# 8_DAC_and_MIC.net
KiCad netlist of a schematic drawn in Altium Designer
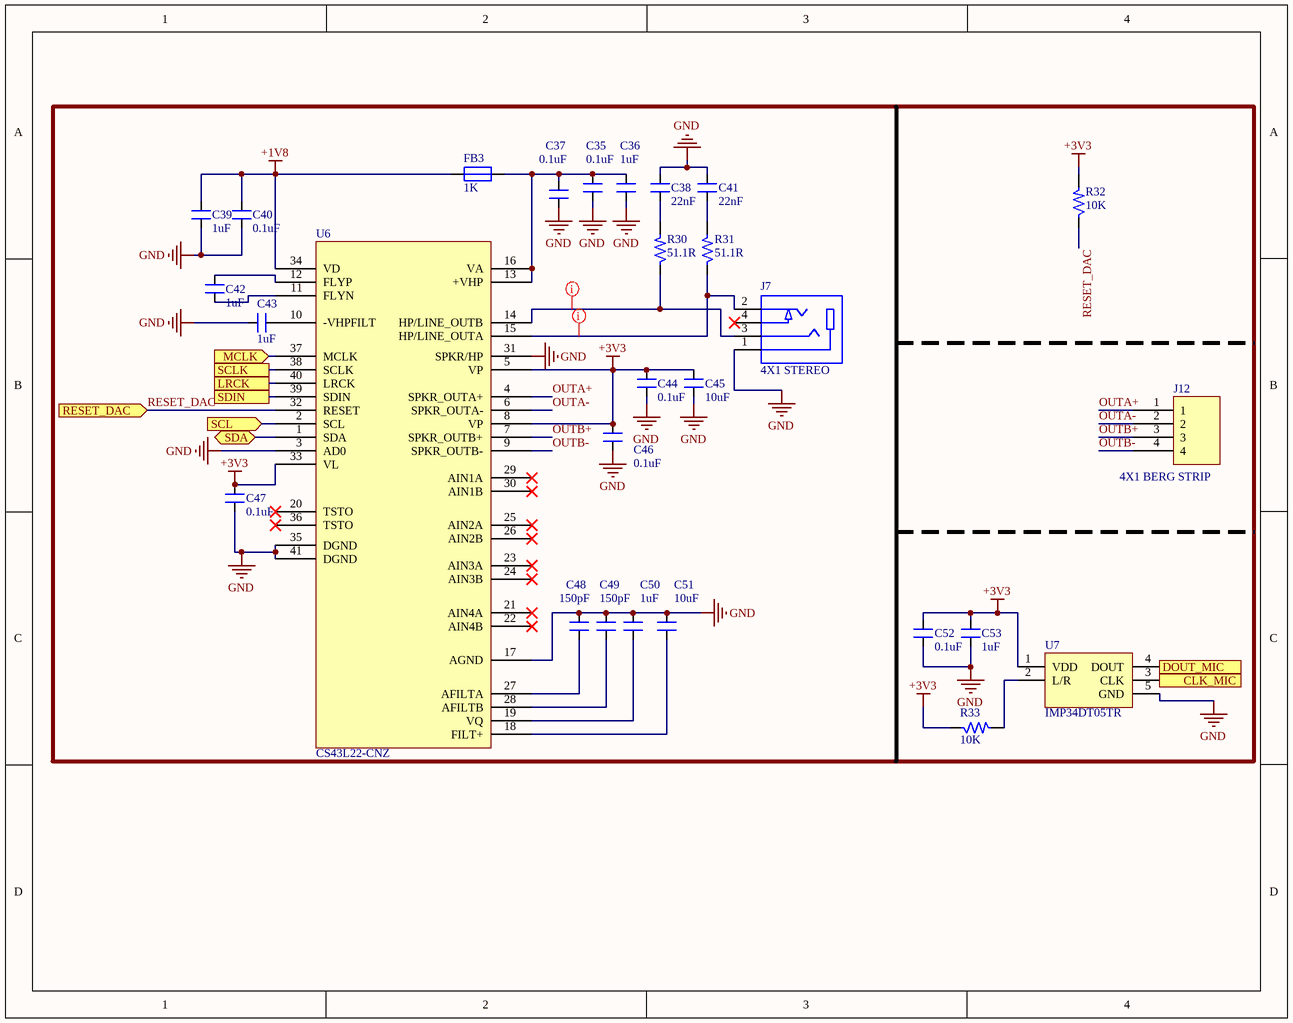
[diagram p0: [8] DAC and MIC.SchDoc]

(export (version "E")
  (design (tool "Eeschema 10.0.6"))
  (components
    (comp (ref "C35")
      (value "0.1uF")
      (footprint "CAP_0805")
      (description "0.1µF ±10% 50V Ceramic Capacitor X7R 0805 (2012 Metric)")
      (fields
        (field (name "MANUFACTURER") "Samsung")
        (field (name "MANUFACTURER PART NUMBER") "CL21B104KBCNNNC")
      )
      (libsource (lib "ESTEEMPCBLIB") (part "CAP_0.1uF-50V-10%-0805"))
    )
    (comp (ref "C36")
      (value "1uF")
      (footprint "CAP_0805")
      (description "1µF ±5% 50V Ceramic Capacitor X7R 0805 (2012 Metric)")
      (fields
        (field (name "MANUFACTURER") "Samsung")
        (field (name "MANUFACTURER PART NUMBER") "CC0805JKX7R9BB105")
      )
      (libsource (lib "ESTEEMPCBLIB") (part "CAP_1uF-50V-5%-0805"))
    )
    (comp (ref "C37")
      (value "0.1uF")
      (footprint "CAP_0805")
      (description "0.1µF ±10% 50V Ceramic Capacitor X7R 0805 (2012 Metric)")
      (fields
        (field (name "MANUFACTURER") "Samsung")
        (field (name "MANUFACTURER PART NUMBER") "CL21B104KBCNNNC")
      )
      (libsource (lib "ESTEEMPCBLIB") (part "CAP_0.1uF-50V-10%-0805"))
    )
    (comp (ref "C38")
      (value "22nF")
      (footprint "CAP_0805")
      (description "0.022µF ±10% 50V Ceramic Capacitor X7R 0805 (2012 Metric)")
      (fields
        (field (name "MANUFACTURER") "Samsung Electro-Mechanics")
        (field (name "MANUFACTURER PART NUMBER") "CL21B223KBANNNC")
      )
      (libsource (lib "ESTEEMPCBLIB") (part "CAP_22nF-50V-10%-0805"))
    )
    (comp (ref "C39")
      (value "1uF")
      (footprint "CAP_0805")
      (description "1µF ±5% 50V Ceramic Capacitor X7R 0805 (2012 Metric)")
      (fields
        (field (name "MANUFACTURER") "Samsung")
        (field (name "MANUFACTURER PART NUMBER") "CC0805JKX7R9BB105")
      )
      (libsource (lib "ESTEEMPCBLIB") (part "CAP_1uF-50V-5%-0805"))
    )
    (comp (ref "C40")
      (value "0.1uF")
      (footprint "CAP_0805")
      (description "0.1µF ±10% 50V Ceramic Capacitor X7R 0805 (2012 Metric)")
      (fields
        (field (name "MANUFACTURER") "Samsung")
        (field (name "MANUFACTURER PART NUMBER") "CL21B104KBCNNNC")
      )
      (libsource (lib "ESTEEMPCBLIB") (part "CAP_0.1uF-50V-10%-0805"))
    )
    (comp (ref "C41")
      (value "22nF")
      (footprint "CAP_0805")
      (description "0.022µF ±10% 50V Ceramic Capacitor X7R 0805 (2012 Metric)")
      (fields
        (field (name "MANUFACTURER") "Samsung Electro-Mechanics")
        (field (name "MANUFACTURER PART NUMBER") "CL21B223KBANNNC")
      )
      (libsource (lib "ESTEEMPCBLIB") (part "CAP_22nF-50V-10%-0805"))
    )
    (comp (ref "C42")
      (value "1uF")
      (footprint "CAP_0805")
      (description "1µF ±5% 50V Ceramic Capacitor X7R 0805 (2012 Metric)")
      (fields
        (field (name "MANUFACTURER") "Samsung")
        (field (name "MANUFACTURER PART NUMBER") "CC0805JKX7R9BB105")
      )
      (libsource (lib "ESTEEMPCBLIB") (part "CAP_1uF-50V-5%-0805"))
    )
    (comp (ref "C43")
      (value "1uF")
      (footprint "CAP_0805")
      (description "1µF ±5% 50V Ceramic Capacitor X7R 0805 (2012 Metric)")
      (fields
        (field (name "MANUFACTURER") "Samsung")
        (field (name "MANUFACTURER PART NUMBER") "CC0805JKX7R9BB105")
      )
      (libsource (lib "ESTEEMPCBLIB") (part "CAP_1uF-50V-5%-0805"))
    )
    (comp (ref "C44")
      (value "0.1uF")
      (footprint "CAP_0805")
      (description "0.1µF ±10% 50V Ceramic Capacitor X7R 0805 (2012 Metric)")
      (fields
        (field (name "MANUFACTURER") "Samsung")
        (field (name "MANUFACTURER PART NUMBER") "CL21B104KBCNNNC")
      )
      (libsource (lib "ESTEEMPCBLIB") (part "CAP_0.1uF-50V-10%-0805"))
    )
    (comp (ref "C45")
      (value "10uF")
      (footprint "CAP_1206")
      (description "10µF ±10% 50V Ceramic Capacitor X7R 1206 (3216 Metric)")
      (fields
        (field (name "MANUFACTURER") "KEMET")
        (field (name "MANUFACTURER PART NUMBER") "CL31B106KBHNNNE")
      )
      (libsource (lib "ESTEEMPCBLIB") (part "CAP_10uF-50V-10%-1206"))
    )
    (comp (ref "C46")
      (value "0.1uF")
      (footprint "CAP_0805")
      (description "0.1µF ±10% 50V Ceramic Capacitor X7R 0805 (2012 Metric)")
      (fields
        (field (name "MANUFACTURER") "Samsung")
        (field (name "MANUFACTURER PART NUMBER") "CL21B104KBCNNNC")
      )
      (libsource (lib "ESTEEMPCBLIB") (part "CAP_0.1uF-50V-10%-0805"))
    )
    (comp (ref "C47")
      (value "0.1uF")
      (footprint "CAP_0805")
      (description "0.1µF ±10% 50V Ceramic Capacitor X7R 0805 (2012 Metric)")
      (fields
        (field (name "MANUFACTURER") "Samsung")
        (field (name "MANUFACTURER PART NUMBER") "CL21B104KBCNNNC")
      )
      (libsource (lib "ESTEEMPCBLIB") (part "CAP_0.1uF-50V-10%-0805"))
    )
    (comp (ref "C48")
      (value "150pF")
      (footprint "CAP_0805")
      (description "150pF ±10% 50V Ceramic Capacitor C0G, NP0 0805 (2012 Metric)")
      (fields
        (field (name "MANUFACTURER") "AVX Corporation")
        (field (name "MANUFACTURER PART NUMBER") "08055A151KAT2A")
      )
      (libsource (lib "ESTEEMPCBLIB") (part "CAP_150pF-50V-10%-0805"))
    )
    (comp (ref "C49")
      (value "150pF")
      (footprint "CAP_0805")
      (description "150pF ±10% 50V Ceramic Capacitor C0G, NP0 0805 (2012 Metric)")
      (fields
        (field (name "MANUFACTURER") "AVX Corporation")
        (field (name "MANUFACTURER PART NUMBER") "08055A151KAT2A")
      )
      (libsource (lib "ESTEEMPCBLIB") (part "CAP_150pF-50V-10%-0805"))
    )
    (comp (ref "C50")
      (value "1uF")
      (footprint "CAP_0805")
      (description "1µF ±5% 50V Ceramic Capacitor X7R 0805 (2012 Metric)")
      (fields
        (field (name "MANUFACTURER") "Samsung")
        (field (name "MANUFACTURER PART NUMBER") "CC0805JKX7R9BB105")
      )
      (libsource (lib "ESTEEMPCBLIB") (part "CAP_1uF-50V-5%-0805"))
    )
    (comp (ref "C51")
      (value "10uF")
      (footprint "CAP_1206")
      (description "10µF ±10% 50V Ceramic Capacitor X7R 1206 (3216 Metric)")
      (fields
        (field (name "MANUFACTURER") "KEMET")
        (field (name "MANUFACTURER PART NUMBER") "CL31B106KBHNNNE")
      )
      (libsource (lib "ESTEEMPCBLIB") (part "CAP_10uF-50V-10%-1206"))
    )
    (comp (ref "C52")
      (value "0.1uF")
      (footprint "CAP_0805")
      (description "0.1µF ±10% 50V Ceramic Capacitor X7R 0805 (2012 Metric)")
      (fields
        (field (name "MANUFACTURER") "Samsung")
        (field (name "MANUFACTURER PART NUMBER") "CL21B104KBCNNNC")
      )
      (libsource (lib "ESTEEMPCBLIB") (part "CAP_0.1uF-50V-10%-0805"))
    )
    (comp (ref "C53")
      (value "1uF")
      (footprint "CAP_0805")
      (description "1µF ±5% 50V Ceramic Capacitor X7R 0805 (2012 Metric)")
      (fields
        (field (name "MANUFACTURER") "Samsung")
        (field (name "MANUFACTURER PART NUMBER") "CC0805JKX7R9BB105")
      )
      (libsource (lib "ESTEEMPCBLIB") (part "CAP_1uF-50V-5%-0805"))
    )
    (comp (ref "FB3")
      (value "1K")
      (footprint "IND_0805")
      (description "1 kOhms @ 100MHz 1 Power Line Ferrite Bead 0805 (2012 Metric) 1.6A")
      (fields
        (field (name "MANUFACTURER") "Laird")
        (field (name "MANUFACTURER PART NUMBER") "BLM21SP102SH1D")
      )
      (libsource (lib "ESTEEMPCBLIB") (part "FB_1K-100MHZ-1.6A-0805"))
    )
    (comp (ref "J7")
      (value "4X1 STEREO")
      (footprint "CON_SJ-2504A-SMT-TR_SMD")
      (fields
        (field (name "MANUFACTURER") "CUI Devices")
        (field (name "MANUFACTURER PART NUMBER") "SJ-2504A-SMT-TR")
      )
      (libsource (lib "ESTEEMPCBLIB") (part "CON-PLG-STEREO_4X1-100-RA-SMD"))
    )
    (comp (ref "J12")
      (value "4X1 BERG STRIP")
      (footprint "CON4_100_40D72_TH_ST_MALE")
      (description "4 Pins, 1 Row 2.54mm Pitch, Straight bergstrip, Male")
      (fields (field (name "MANUFACTURER") "NA"))
      (libsource (lib "ESTEEMPCBLIB") (part "CON-BS-PLG_4X1-100-ST-TH"))
    )
    (comp (ref "R30")
      (value "51.1R")
      (footprint "RES_0603")
      (description "51.1 Ohms ±1% 0.1W, 1/10W Chip Resistor 0603 (1608 Metric) Thick Film")
      (fields
        (field (name "MANUFACTURER") "Vishay Dale")
        (field (name "MANUFACTURER PART NUMBER") "CRCW060351R1FKEAC")
      )
      (libsource (lib "ESTEEMPCBLIB") (part "RES_51.1R-0.1W-1%-0603"))
    )
    (comp (ref "R31")
      (value "51.1R")
      (footprint "RES_0603")
      (description "51.1 Ohms ±1% 0.1W, 1/10W Chip Resistor 0603 (1608 Metric) Thick Film")
      (fields
        (field (name "MANUFACTURER") "Vishay Dale")
        (field (name "MANUFACTURER PART NUMBER") "CRCW060351R1FKEAC")
      )
      (libsource (lib "ESTEEMPCBLIB") (part "RES_51.1R-0.1W-1%-0603"))
    )
    (comp (ref "R32")
      (value "10K")
      (footprint "RES_0603")
      (description "10 kOhms ±1% 0.1W, 1/10W Chip Resistor 0603 (1608 Metric) Automotive AEC-Q200 Thick Film")
      (fields (field (name "MANUFACTURER") "Walsin") (field (name "MANUFACTURER PART NUMBER") "WR06X1002FTL"))
      (libsource (lib "ESTEEMPCBLIB") (part "RES_10K-0.1W-1%-0603"))
    )
    (comp (ref "R33")
      (value "10K")
      (footprint "RES_0603")
      (description "10 kOhms ±1% 0.1W, 1/10W Chip Resistor 0603 (1608 Metric) Automotive AEC-Q200 Thick Film")
      (fields (field (name "MANUFACTURER") "Walsin") (field (name "MANUFACTURER PART NUMBER") "WR06X1002FTL"))
      (libsource (lib "ESTEEMPCBLIB") (part "RES_10K-0.1W-1%-0603"))
    )
    (comp (ref "U6")
      (value "CS43L22-CNZ")
      (footprint "QFN40_19_284_33X9_SMD")
      (description "Audio D/A Converter ICs Low Power Stereo DAC w/ClassD Spkr Driver")
      (fields (field (name "MANUFACTURER") "Cirrus Logic"))
      (libsource (lib "ESTEEMPCBLIB") (part "IC_CS43L22"))
    )
    (comp (ref "U7")
      (value "IMP34DT05TR")
      (footprint "HCLGA-4_53_137_15X37_SMD")
      (description "MEMS Microphones AUTO & INDUSTRIAL SENSORS")
      (fields (field (name "MANUFACTURER") "STMicroelectronics"))
      (libsource (lib "ESTEEMPCBLIB") (part "IC_IMP34DT05TR"))
    )
  )
  (nets
    (net (code "1") (name "+1V8") (class "Default")
      (node (ref "C39") (pin "2") (pinfunction "2_2") (pintype "passive"))
      (node (ref "C40") (pin "2") (pinfunction "2_2") (pintype "passive"))
      (node (ref "FB3") (pin "1") (pinfunction "1_1") (pintype "passive"))
      (node (ref "U6") (pin "34") (pinfunction "VD_34") (pintype "passive"))
    )
    (net (code "2") (name "+3V3") (class "Default")
      (node (ref "C44") (pin "2") (pinfunction "2_2") (pintype "passive"))
      (node (ref "C45") (pin "2") (pinfunction "2_2") (pintype "passive"))
      (node (ref "C46") (pin "2") (pinfunction "2_2") (pintype "passive"))
      (node (ref "C47") (pin "2") (pinfunction "2_2") (pintype "passive"))
      (node (ref "C52") (pin "2") (pinfunction "2_2") (pintype "passive"))
      (node (ref "C53") (pin "2") (pinfunction "2_2") (pintype "passive"))
      (node (ref "R32") (pin "2") (pinfunction "2_2") (pintype "passive"))
      (node (ref "R33") (pin "1") (pinfunction "1_1") (pintype "passive"))
      (node (ref "U6") (pin "33") (pinfunction "VL_33") (pintype "passive"))
      (node (ref "U6") (pin "5") (pinfunction "VP_5") (pintype "passive"))
      (node (ref "U6") (pin "8") (pinfunction "VP_8") (pintype "passive"))
      (node (ref "U7") (pin "1") (pinfunction "VDD_1") (pintype "passive"))
    )
    (net (code "3") (name "/CLK_MIC") (class "Default")
      (node (ref "U7") (pin "3") (pinfunction "CLK_3") (pintype "passive"))
    )
    (net (code "4") (name "/DOUT_MIC") (class "Default")
      (node (ref "U7") (pin "4") (pinfunction "DOUT_4") (pintype "passive"))
    )
    (net (code "5") (name "/LRCK") (class "Default")
      (node (ref "U6") (pin "40") (pinfunction "LRCK_40") (pintype "passive"))
    )
    (net (code "6") (name "/MCLK") (class "Default")
      (node (ref "U6") (pin "37") (pinfunction "MCLK_37") (pintype "passive"))
    )
    (net (code "7") (name "/OUTA+") (class "Default")
      (node (ref "J12") (pin "1") (pinfunction "1_1") (pintype "passive"))
      (node (ref "U6") (pin "4") (pinfunction "SPKR_OUTA+_4") (pintype "passive"))
    )
    (net (code "8") (name "/OUTA-") (class "Default")
      (node (ref "J12") (pin "2") (pinfunction "2_2") (pintype "passive"))
      (node (ref "U6") (pin "6") (pinfunction "SPKR_OUTA-_6") (pintype "passive"))
    )
    (net (code "9") (name "/OUTB+") (class "Default")
      (node (ref "J12") (pin "3") (pinfunction "3_3") (pintype "passive"))
      (node (ref "U6") (pin "7") (pinfunction "SPKR_OUTB+_7") (pintype "passive"))
    )
    (net (code "10") (name "/OUTB-") (class "Default")
      (node (ref "J12") (pin "4") (pinfunction "4_4") (pintype "passive"))
      (node (ref "U6") (pin "9") (pinfunction "SPKR_OUTB-_9") (pintype "passive"))
    )
    (net (code "11") (name "/RESET_DAC") (class "Default")
      (node (ref "R32") (pin "1") (pinfunction "1_1") (pintype "passive"))
      (node (ref "U6") (pin "32") (pinfunction "RESET_32") (pintype "passive"))
    )
    (net (code "12") (name "/SCL") (class "Default")
      (node (ref "U6") (pin "2") (pinfunction "SCL_2") (pintype "passive"))
    )
    (net (code "13") (name "/SCLK") (class "Default")
      (node (ref "U6") (pin "38") (pinfunction "SCLK_38") (pintype "passive"))
    )
    (net (code "14") (name "/SDA") (class "Default")
      (node (ref "U6") (pin "1") (pinfunction "SDA_1") (pintype "passive"))
    )
    (net (code "15") (name "/SDIN") (class "Default")
      (node (ref "U6") (pin "39") (pinfunction "SDIN_39") (pintype "passive"))
    )
    (net (code "16") (name "GND") (class "Default")
      (node (ref "C35") (pin "1") (pinfunction "1_1") (pintype "passive"))
      (node (ref "C36") (pin "1") (pinfunction "1_1") (pintype "passive"))
      (node (ref "C37") (pin "1") (pinfunction "1_1") (pintype "passive"))
      (node (ref "C38") (pin "2") (pinfunction "2_2") (pintype "passive"))
      (node (ref "C39") (pin "1") (pinfunction "1_1") (pintype "passive"))
      (node (ref "C40") (pin "1") (pinfunction "1_1") (pintype "passive"))
      (node (ref "C41") (pin "2") (pinfunction "2_2") (pintype "passive"))
      (node (ref "C43") (pin "2") (pinfunction "2_2") (pintype "passive"))
      (node (ref "C44") (pin "1") (pinfunction "1_1") (pintype "passive"))
      (node (ref "C45") (pin "1") (pinfunction "1_1") (pintype "passive"))
      (node (ref "C46") (pin "1") (pinfunction "1_1") (pintype "passive"))
      (node (ref "C47") (pin "1") (pinfunction "1_1") (pintype "passive"))
      (node (ref "C48") (pin "1") (pinfunction "1_1") (pintype "passive"))
      (node (ref "C49") (pin "1") (pinfunction "1_1") (pintype "passive"))
      (node (ref "C50") (pin "2") (pinfunction "2_2") (pintype "passive"))
      (node (ref "C51") (pin "2") (pinfunction "2_2") (pintype "passive"))
      (node (ref "C52") (pin "1") (pinfunction "1_1") (pintype "passive"))
      (node (ref "C53") (pin "1") (pinfunction "1_1") (pintype "passive"))
      (node (ref "J7") (pin "1") (pinfunction "1_1") (pintype "passive"))
      (node (ref "U6") (pin "17") (pinfunction "AGND_17") (pintype "passive"))
      (node (ref "U6") (pin "3") (pinfunction "AD0_3") (pintype "passive"))
      (node (ref "U6") (pin "31") (pinfunction "SPKR/HP_31") (pintype "passive"))
      (node (ref "U6") (pin "35") (pinfunction "DGND_35") (pintype "passive"))
      (node (ref "U6") (pin "41") (pinfunction "DGND_41") (pintype "passive"))
      (node (ref "U7") (pin "5") (pinfunction "GND_5") (pintype "passive"))
    )
    (net (code "17") (name "Net-(C38-Pad1)") (class "Default")
      (node (ref "C38") (pin "1") (pinfunction "1_1") (pintype "passive"))
      (node (ref "R30") (pin "2") (pinfunction "2_2") (pintype "passive"))
    )
    (net (code "18") (name "Net-(C41-Pad1)") (class "Default")
      (node (ref "C41") (pin "1") (pinfunction "1_1") (pintype "passive"))
      (node (ref "R31") (pin "2") (pinfunction "2_2") (pintype "passive"))
    )
    (net (code "19") (name "Net-(U6-+VHP)") (class "Default")
      (node (ref "C35") (pin "2") (pinfunction "2_2") (pintype "passive"))
      (node (ref "C36") (pin "2") (pinfunction "2_2") (pintype "passive"))
      (node (ref "C37") (pin "2") (pinfunction "2_2") (pintype "passive"))
      (node (ref "FB3") (pin "2") (pinfunction "2_2") (pintype "passive"))
      (node (ref "U6") (pin "13") (pinfunction "+VHP_13") (pintype "passive"))
      (node (ref "U6") (pin "16") (pinfunction "VA_16") (pintype "passive"))
    )
    (net (code "20") (name "Net-(U6--VHPFILT)") (class "Default")
      (node (ref "C43") (pin "1") (pinfunction "1_1") (pintype "passive"))
      (node (ref "U6") (pin "10") (pinfunction "-VHPFILT_10") (pintype "passive"))
    )
    (net (code "21") (name "Net-(U6-AFILTA)") (class "Default")
      (node (ref "C48") (pin "2") (pinfunction "2_2") (pintype "passive"))
      (node (ref "U6") (pin "27") (pinfunction "AFILTA_27") (pintype "passive"))
    )
    (net (code "22") (name "Net-(U6-AFILTB)") (class "Default")
      (node (ref "C49") (pin "2") (pinfunction "2_2") (pintype "passive"))
      (node (ref "U6") (pin "28") (pinfunction "AFILTB_28") (pintype "passive"))
    )
    (net (code "23") (name "Net-(U6-FILT+)") (class "Default")
      (node (ref "C51") (pin "1") (pinfunction "1_1") (pintype "passive"))
      (node (ref "U6") (pin "18") (pinfunction "FILT+_18") (pintype "passive"))
    )
    (net (code "24") (name "Net-(U6-FLYN)") (class "Default")
      (node (ref "C42") (pin "1") (pinfunction "1_1") (pintype "passive"))
      (node (ref "U6") (pin "11") (pinfunction "FLYN_11") (pintype "passive"))
    )
    (net (code "25") (name "Net-(U6-FLYP)") (class "Default")
      (node (ref "C42") (pin "2") (pinfunction "2_2") (pintype "passive"))
      (node (ref "U6") (pin "12") (pinfunction "FLYP_12") (pintype "passive"))
    )
    (net (code "26") (name "Net-(U6-HP{slash}LINE_OUTA)") (class "Default")
      (node (ref "J7") (pin "2") (pinfunction "2_2") (pintype "passive"))
      (node (ref "R31") (pin "1") (pinfunction "1_1") (pintype "passive"))
      (node (ref "U6") (pin "15") (pinfunction "HP/LINE_OUTA_15") (pintype "passive"))
    )
    (net (code "27") (name "Net-(U6-HP{slash}LINE_OUTB)") (class "Default")
      (node (ref "J7") (pin "3") (pinfunction "3_3") (pintype "passive"))
      (node (ref "R30") (pin "1") (pinfunction "1_1") (pintype "passive"))
      (node (ref "U6") (pin "14") (pinfunction "HP/LINE_OUTB_14") (pintype "passive"))
    )
    (net (code "28") (name "Net-(U6-VQ)") (class "Default")
      (node (ref "C50") (pin "1") (pinfunction "1_1") (pintype "passive"))
      (node (ref "U6") (pin "19") (pinfunction "VQ_19") (pintype "passive"))
    )
    (net (code "29") (name "Net-(U7-L{slash}R)") (class "Default")
      (node (ref "R33") (pin "2") (pinfunction "2_2") (pintype "passive"))
      (node (ref "U7") (pin "2") (pinfunction "L/R_2") (pintype "passive"))
    )
    (net (code "30") (name "unconnected-(J7-Pad4)") (class "Default")
      (node (ref "J7") (pin "4") (pinfunction "4_4") (pintype "passive+no_connect"))
    )
    (net (code "31") (name "unconnected-(U6-AIN1A-Pad29)") (class "Default")
      (node (ref "U6") (pin "29") (pinfunction "AIN1A_29") (pintype "passive+no_connect"))
    )
    (net (code "32") (name "unconnected-(U6-AIN1B-Pad30)") (class "Default")
      (node (ref "U6") (pin "30") (pinfunction "AIN1B_30") (pintype "passive+no_connect"))
    )
    (net (code "33") (name "unconnected-(U6-AIN2A-Pad25)") (class "Default")
      (node (ref "U6") (pin "25") (pinfunction "AIN2A_25") (pintype "passive+no_connect"))
    )
    (net (code "34") (name "unconnected-(U6-AIN2B-Pad26)") (class "Default")
      (node (ref "U6") (pin "26") (pinfunction "AIN2B_26") (pintype "passive+no_connect"))
    )
    (net (code "35") (name "unconnected-(U6-AIN3A-Pad23)") (class "Default")
      (node (ref "U6") (pin "23") (pinfunction "AIN3A_23") (pintype "passive+no_connect"))
    )
    (net (code "36") (name "unconnected-(U6-AIN3B-Pad24)") (class "Default")
      (node (ref "U6") (pin "24") (pinfunction "AIN3B_24") (pintype "passive+no_connect"))
    )
    (net (code "37") (name "unconnected-(U6-AIN4A-Pad21)") (class "Default")
      (node (ref "U6") (pin "21") (pinfunction "AIN4A_21") (pintype "passive+no_connect"))
    )
    (net (code "38") (name "unconnected-(U6-AIN4B-Pad22)") (class "Default")
      (node (ref "U6") (pin "22") (pinfunction "AIN4B_22") (pintype "passive+no_connect"))
    )
    (net (code "39") (name "unconnected-(U6-TSTO-Pad20)") (class "Default")
      (node (ref "U6") (pin "20") (pinfunction "TSTO_20") (pintype "passive+no_connect"))
    )
    (net (code "40") (name "unconnected-(U6-TSTO-Pad36)") (class "Default")
      (node (ref "U6") (pin "36") (pinfunction "TSTO_36") (pintype "passive+no_connect"))
    )
  )
)
